# AD9910.net
KiCad netlist of a schematic drawn in Altium Designer
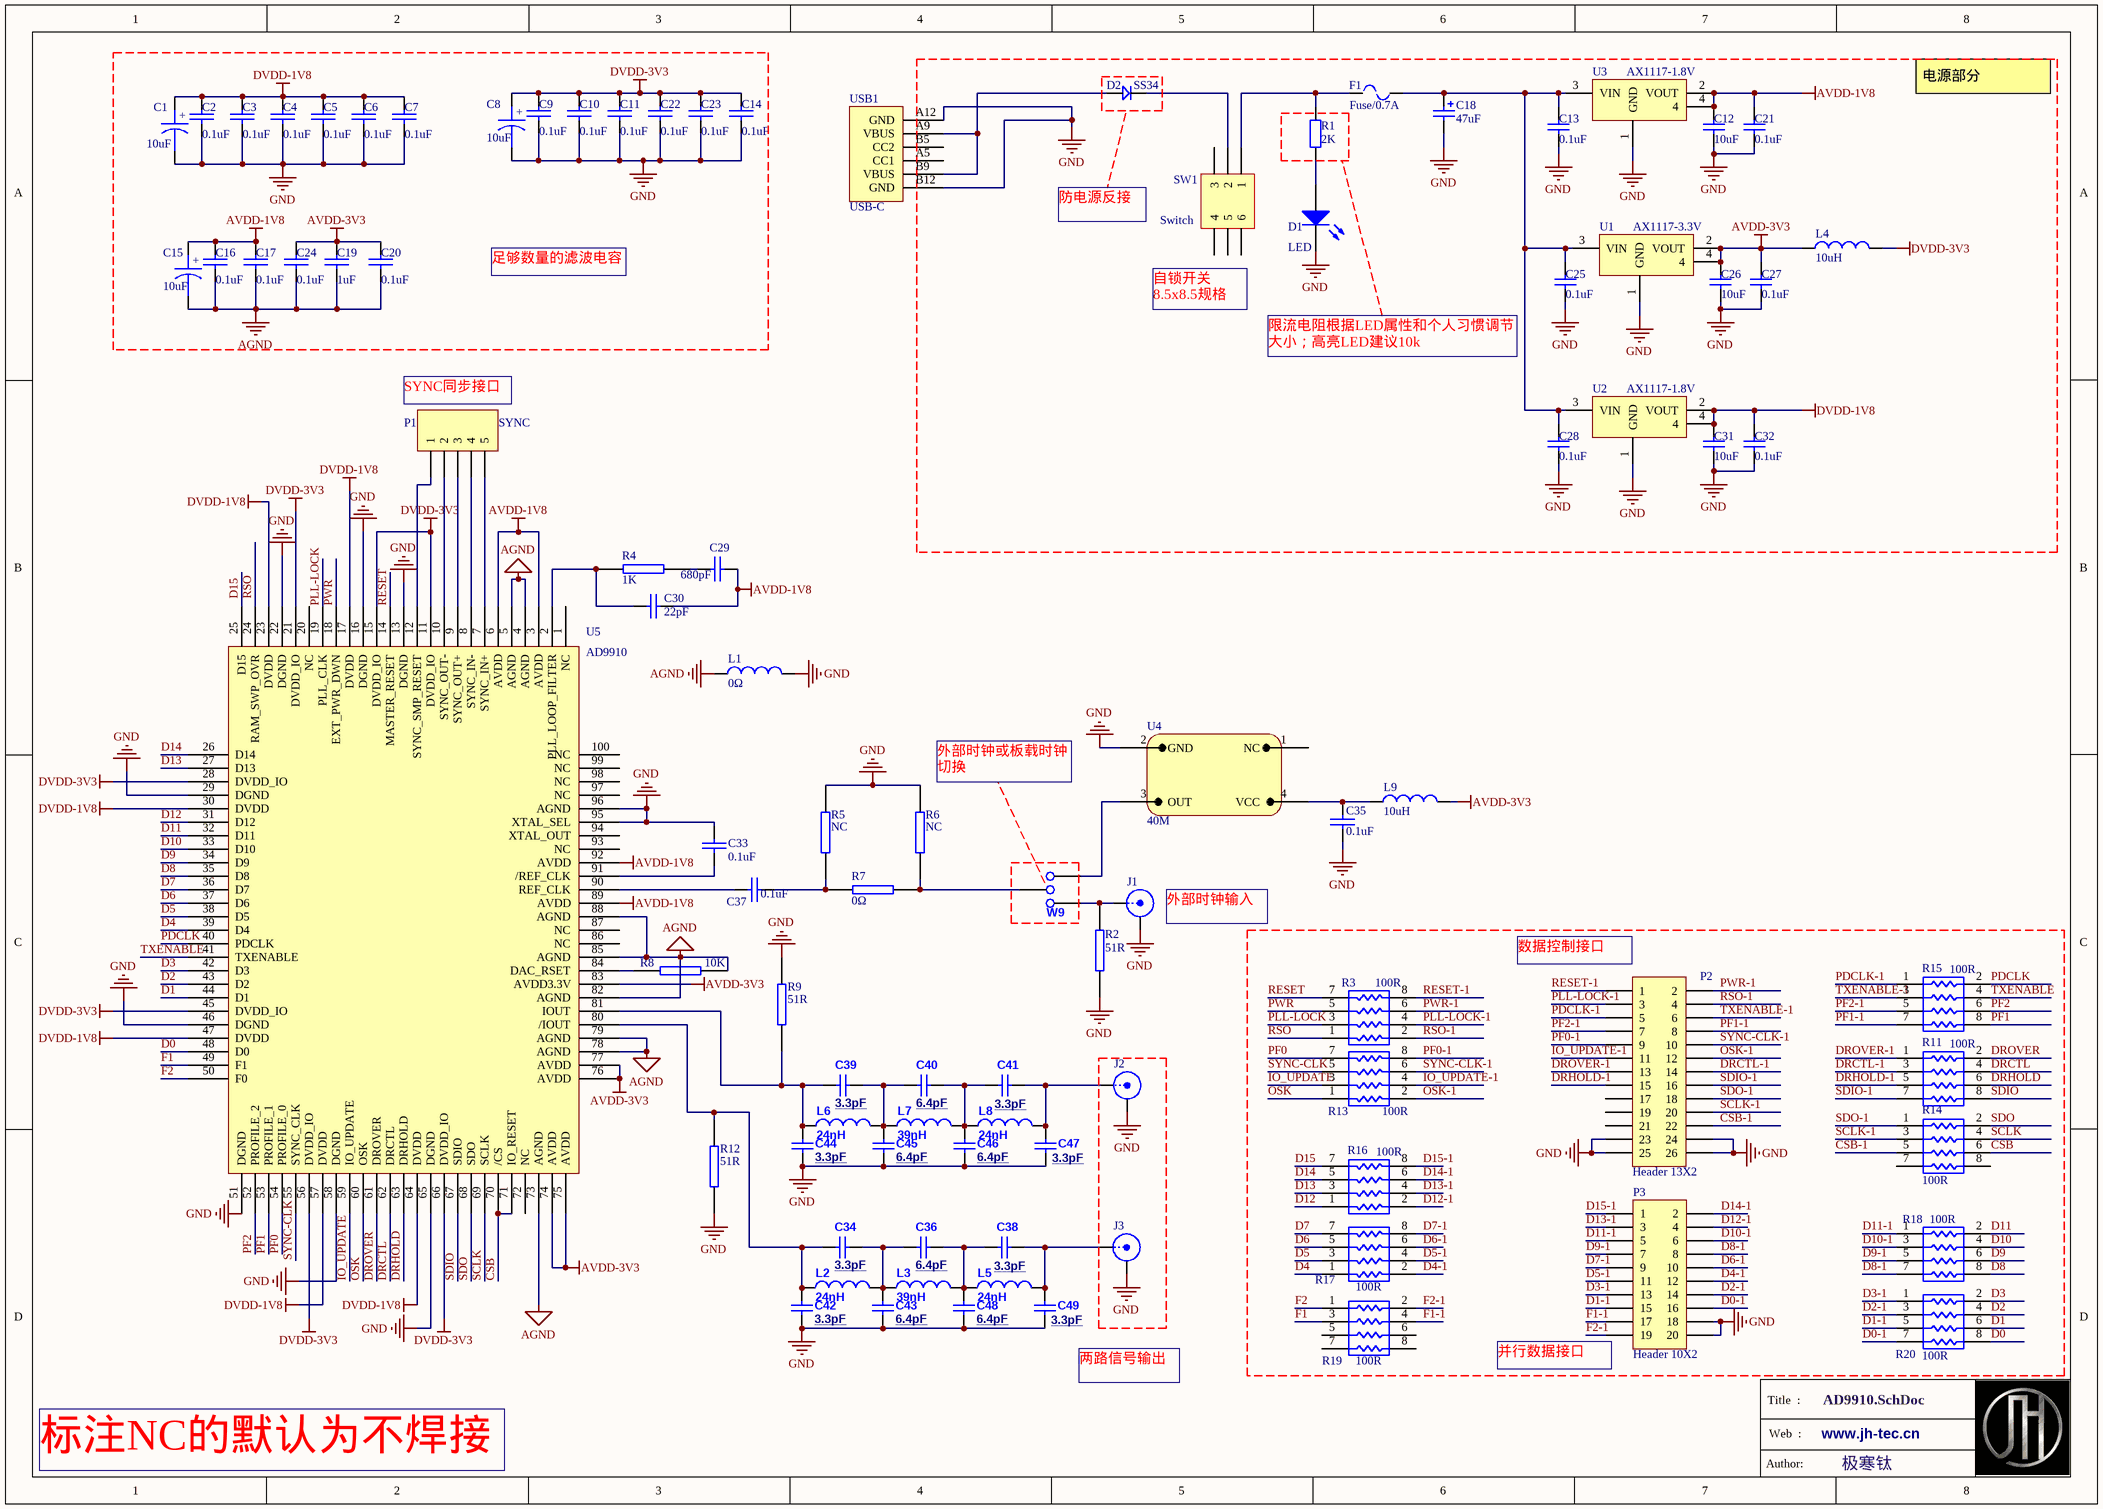
[diagram p0: AD9910.SchDoc]

(export (version "E")
  (design (tool "Eeschema 10.0.6"))
  (components
    (comp (ref "C1")
      (value "10uF")
      (footprint "JH_PCB:C3216")
      (description "Capacitor")
      (libsource (lib "*") (part "CAPACITOR POL"))
    )
    (comp (ref "C2")
      (value "0.1uF")
      (footprint "JH_PCB:C0603")
      (description "Capacitor")
      (libsource (lib "*") (part "CAP"))
    )
    (comp (ref "C3")
      (value "0.1uF")
      (footprint "JH_PCB:C0603")
      (description "Capacitor")
      (libsource (lib "*") (part "CAP"))
    )
    (comp (ref "C4")
      (value "0.1uF")
      (footprint "JH_PCB:C0603")
      (description "Capacitor")
      (libsource (lib "*") (part "CAP"))
    )
    (comp (ref "C5")
      (value "0.1uF")
      (footprint "JH_PCB:C0603")
      (description "Capacitor")
      (libsource (lib "*") (part "CAP"))
    )
    (comp (ref "C6")
      (value "0.1uF")
      (footprint "JH_PCB:C0603")
      (description "Capacitor")
      (libsource (lib "*") (part "CAP"))
    )
    (comp (ref "C7")
      (value "0.1uF")
      (footprint "JH_PCB:C0603")
      (description "Capacitor")
      (libsource (lib "*") (part "CAP"))
    )
    (comp (ref "C8")
      (value "10uF")
      (footprint "JH_PCB:C3216")
      (description "Capacitor")
      (libsource (lib "*") (part "CAPACITOR POL"))
    )
    (comp (ref "C9")
      (value "0.1uF")
      (footprint "JH_PCB:C0603")
      (description "Capacitor")
      (libsource (lib "*") (part "CAP"))
    )
    (comp (ref "C10")
      (value "0.1uF")
      (footprint "JH_PCB:C0603")
      (description "Capacitor")
      (libsource (lib "*") (part "CAP"))
    )
    (comp (ref "C11")
      (value "0.1uF")
      (footprint "JH_PCB:C0603")
      (description "Capacitor")
      (libsource (lib "*") (part "CAP"))
    )
    (comp (ref "C12")
      (value "10uF")
      (footprint "JH_PCB:C3216")
      (description "Capacitor (Semiconductor SIM Model)")
      (fields (field (name "PUBLISHER") "Altium Limited"))
      (libsource (lib "mylib") (part "Cap Semi"))
    )
    (comp (ref "C13")
      (value "0.1uF")
      (footprint "JH_PCB:C0603")
      (description "Capacitor (Semiconductor SIM Model)")
      (fields (field (name "PUBLISHER") "Altium Limited"))
      (libsource (lib "mylib") (part "Cap Semi"))
    )
    (comp (ref "C14")
      (value "0.1uF")
      (footprint "JH_PCB:C0603")
      (description "Capacitor")
      (libsource (lib "*") (part "CAP"))
    )
    (comp (ref "C15")
      (value "10uF")
      (footprint "JH_PCB:C3216")
      (description "Capacitor")
      (libsource (lib "*") (part "CAPACITOR POL"))
    )
    (comp (ref "C16")
      (value "0.1uF")
      (footprint "JH_PCB:C0603")
      (description "Capacitor")
      (libsource (lib "*") (part "CAP"))
    )
    (comp (ref "C17")
      (value "0.1uF")
      (footprint "JH_PCB:C0603")
      (description "Capacitor")
      (libsource (lib "*") (part "CAP"))
    )
    (comp (ref "C18")
      (value "47uF")
      (footprint "JH_PCB:C7343")
      (description "Polarized Capacitor (Surface Mount)")
      (fields (field (name "PUBLISHER") "Altium Limited"))
      (libsource (lib "mylib") (part "Cap Pol3_1"))
    )
    (comp (ref "C19")
      (value "1uF")
      (footprint "JH_PCB:C0603")
      (description "Capacitor")
      (libsource (lib "*") (part "CAP"))
    )
    (comp (ref "C20")
      (value "0.1uF")
      (footprint "JH_PCB:C0603")
      (description "Capacitor")
      (libsource (lib "*") (part "CAP"))
    )
    (comp (ref "C21")
      (value "0.1uF")
      (footprint "JH_PCB:C0603")
      (description "Capacitor (Semiconductor SIM Model)")
      (fields (field (name "PUBLISHER") "Altium Limited"))
      (libsource (lib "mylib") (part "Cap Semi"))
    )
    (comp (ref "C22")
      (value "0.1uF")
      (footprint "JH_PCB:C0603")
      (description "Capacitor")
      (libsource (lib "*") (part "CAP"))
    )
    (comp (ref "C23")
      (value "0.1uF")
      (footprint "JH_PCB:C0603")
      (description "Capacitor")
      (libsource (lib "*") (part "CAP"))
    )
    (comp (ref "C24")
      (value "0.1uF")
      (footprint "JH_PCB:C0603")
      (description "Capacitor")
      (libsource (lib "*") (part "CAP"))
    )
    (comp (ref "C25")
      (value "0.1uF")
      (footprint "JH_PCB:C0603")
      (description "Capacitor (Semiconductor SIM Model)")
      (fields (field (name "PUBLISHER") "Altium Limited"))
      (libsource (lib "mylib") (part "Cap Semi"))
    )
    (comp (ref "C26")
      (value "10uF")
      (footprint "JH_PCB:C3216")
      (description "Capacitor (Semiconductor SIM Model)")
      (fields (field (name "PUBLISHER") "Altium Limited"))
      (libsource (lib "mylib") (part "Cap Semi"))
    )
    (comp (ref "C27")
      (value "0.1uF")
      (footprint "JH_PCB:C0603")
      (description "Capacitor (Semiconductor SIM Model)")
      (fields (field (name "PUBLISHER") "Altium Limited"))
      (libsource (lib "mylib") (part "Cap Semi"))
    )
    (comp (ref "C28")
      (value "0.1uF")
      (footprint "JH_PCB:C0603")
      (description "Capacitor (Semiconductor SIM Model)")
      (fields (field (name "PUBLISHER") "Altium Limited"))
      (libsource (lib "mylib") (part "Cap Semi"))
    )
    (comp (ref "C29")
      (value "680pF")
      (footprint "JH_PCB:C0603")
      (description "Capacitor")
      (libsource (lib "*") (part "CAP"))
    )
    (comp (ref "C30")
      (value "22pF")
      (footprint "JH_PCB:C0603")
      (description "Capacitor")
      (libsource (lib "*") (part "CAP"))
    )
    (comp (ref "C31")
      (value "10uF")
      (footprint "JH_PCB:C3216")
      (description "Capacitor (Semiconductor SIM Model)")
      (fields (field (name "PUBLISHER") "Altium Limited"))
      (libsource (lib "mylib") (part "Cap Semi"))
    )
    (comp (ref "C32")
      (value "0.1uF")
      (footprint "JH_PCB:C0603")
      (description "Capacitor (Semiconductor SIM Model)")
      (fields (field (name "PUBLISHER") "Altium Limited"))
      (libsource (lib "mylib") (part "Cap Semi"))
    )
    (comp (ref "C33")
      (value "0.1uF")
      (footprint "JH_PCB:C0603")
      (description "Capacitor")
      (libsource (lib "*") (part "CAP"))
    )
    (comp (ref "C34")
      (value "3.3pF")
      (footprint "JH_PCB:C0603")
      (description "Capacitor")
      (fields (field (name "PUBLISHER") "Altium Limited"))
      (libsource (lib "Miscellaneous Devices") (part "Cap"))
    )
    (comp (ref "C35")
      (value "0.1uF")
      (footprint "JH_PCB:C0603")
      (description "Capacitor")
      (libsource (lib "*") (part "CAP"))
    )
    (comp (ref "C36")
      (value "6.4pF")
      (footprint "JH_PCB:C0603")
      (description "Capacitor")
      (fields (field (name "PUBLISHER") "Altium Limited"))
      (libsource (lib "Miscellaneous Devices") (part "Cap"))
    )
    (comp (ref "C37")
      (value "0.1uF")
      (footprint "JH_PCB:C0603")
      (description "Capacitor")
      (libsource (lib "*") (part "CAP"))
    )
    (comp (ref "C38")
      (value "3.3pF")
      (footprint "JH_PCB:C0603")
      (description "Capacitor")
      (fields (field (name "PUBLISHER") "Altium Limited"))
      (libsource (lib "Miscellaneous Devices") (part "Cap"))
    )
    (comp (ref "C39")
      (value "3.3pF")
      (footprint "JH_PCB:C0603")
      (description "Capacitor")
      (fields (field (name "PUBLISHER") "Altium Limited"))
      (libsource (lib "Miscellaneous Devices") (part "Cap"))
    )
    (comp (ref "C40")
      (value "6.4pF")
      (footprint "JH_PCB:C0603")
      (description "Capacitor")
      (fields (field (name "PUBLISHER") "Altium Limited"))
      (libsource (lib "Miscellaneous Devices") (part "Cap"))
    )
    (comp (ref "C41")
      (value "3.3pF")
      (footprint "JH_PCB:C0603")
      (description "Capacitor")
      (fields (field (name "PUBLISHER") "Altium Limited"))
      (libsource (lib "Miscellaneous Devices") (part "Cap"))
    )
    (comp (ref "C42")
      (value "3.3pF")
      (footprint "JH_PCB:C0603")
      (description "Capacitor")
      (fields (field (name "PUBLISHER") "Altium Limited"))
      (libsource (lib "Miscellaneous Devices") (part "Cap"))
    )
    (comp (ref "C43")
      (value "6.4pF")
      (footprint "JH_PCB:C0603")
      (description "Capacitor")
      (fields (field (name "PUBLISHER") "Altium Limited"))
      (libsource (lib "Miscellaneous Devices") (part "Cap"))
    )
    (comp (ref "C44")
      (value "3.3pF")
      (footprint "JH_PCB:C0603")
      (description "Capacitor")
      (fields (field (name "PUBLISHER") "Altium Limited"))
      (libsource (lib "Miscellaneous Devices") (part "Cap"))
    )
    (comp (ref "C45")
      (value "6.4pF")
      (footprint "JH_PCB:C0603")
      (description "Capacitor")
      (fields (field (name "PUBLISHER") "Altium Limited"))
      (libsource (lib "Miscellaneous Devices") (part "Cap"))
    )
    (comp (ref "C46")
      (value "6.4pF")
      (footprint "JH_PCB:C0603")
      (description "Capacitor")
      (fields (field (name "PUBLISHER") "Altium Limited"))
      (libsource (lib "Miscellaneous Devices") (part "Cap"))
    )
    (comp (ref "C47")
      (value "3.3pF")
      (footprint "JH_PCB:C0603")
      (description "Capacitor")
      (fields (field (name "PUBLISHER") "Altium Limited"))
      (libsource (lib "Miscellaneous Devices") (part "Cap"))
    )
    (comp (ref "C48")
      (value "6.4pF")
      (footprint "JH_PCB:C0603")
      (description "Capacitor")
      (fields (field (name "PUBLISHER") "Altium Limited"))
      (libsource (lib "Miscellaneous Devices") (part "Cap"))
    )
    (comp (ref "C49")
      (value "3.3pF")
      (footprint "JH_PCB:C0603")
      (description "Capacitor")
      (fields (field (name "PUBLISHER") "Altium Limited"))
      (libsource (lib "Miscellaneous Devices") (part "Cap"))
    )
    (comp (ref "D1")
      (value "LED")
      (footprint "JH_PCB:LED_GREEN_0603")
      (fields (field (name "PUBLISHER") "Altium Limited"))
      (libsource (lib "Xiaowei") (part "LED"))
    )
    (comp (ref "D2")
      (value "SS34")
      (footprint "JH_PCB:DO-214AC")
      (description "1N4148")
      (libsource (lib "ATK-SIM900A") (part "D"))
    )
    (comp (ref "F1") (value "Fuse/0.7A") (footprint "JH_PCB:1812") (libsource (lib "常用sch") (part "Fuse")))
    (comp (ref "J1")
      (value "SMB")
      (footprint "JH_PCB:SMA_RJ45")
      (description "SMB Straight Connector")
      (fields (field (name "PUBLISHER") "Altium Limited"))
      (libsource (lib "Miscellaneous Connectors") (part "SMB"))
    )
    (comp (ref "J2")
      (value "SMB")
      (footprint "JH_PCB:SMA_3D")
      (description "SMB Straight Connector")
      (fields (field (name "PUBLISHER") "Altium Limited"))
      (libsource (lib "Miscellaneous Connectors") (part "SMB"))
    )
    (comp (ref "J3")
      (value "SMB")
      (footprint "JH_PCB:SMA_3D")
      (description "SMB Straight Connector")
      (fields (field (name "PUBLISHER") "Altium Limited"))
      (libsource (lib "Miscellaneous Connectors") (part "SMB"))
    )
    (comp (ref "L1")
      (value "0Ω")
      (footprint "JH_PCB:L0805")
      (description "Inductor")
      (fields (field (name "PUBLISHER") "Altium Limited"))
      (libsource (lib "Miscellaneous Devices") (part "Inductor"))
    )
    (comp (ref "L2")
      (value "24nH")
      (footprint "JH_PCB:L0603")
      (description "Inductor")
      (fields (field (name "PUBLISHER") "Altium Limited"))
      (libsource (lib "Miscellaneous Devices") (part "Inductor"))
    )
    (comp (ref "L3")
      (value "39nH")
      (footprint "JH_PCB:L0603")
      (description "Inductor")
      (fields (field (name "PUBLISHER") "Altium Limited"))
      (libsource (lib "Miscellaneous Devices") (part "Inductor"))
    )
    (comp (ref "L4")
      (value "10uH")
      (footprint "JH_PCB:L0805")
      (description "Inductor")
      (fields (field (name "PUBLISHER") "Altium Limited"))
      (libsource (lib "Miscellaneous Devices") (part "Inductor"))
    )
    (comp (ref "L5")
      (value "24nH")
      (footprint "JH_PCB:L0603")
      (description "Inductor")
      (fields (field (name "PUBLISHER") "Altium Limited"))
      (libsource (lib "Miscellaneous Devices") (part "Inductor"))
    )
    (comp (ref "L6")
      (value "24nH")
      (footprint "JH_PCB:L0603")
      (description "Inductor")
      (fields (field (name "PUBLISHER") "Altium Limited"))
      (libsource (lib "Miscellaneous Devices") (part "Inductor"))
    )
    (comp (ref "L7")
      (value "39nH")
      (footprint "JH_PCB:L0603")
      (description "Inductor")
      (fields (field (name "PUBLISHER") "Altium Limited"))
      (libsource (lib "Miscellaneous Devices") (part "Inductor"))
    )
    (comp (ref "L8")
      (value "24nH")
      (footprint "JH_PCB:L0603")
      (description "Inductor")
      (fields (field (name "PUBLISHER") "Altium Limited"))
      (libsource (lib "Miscellaneous Devices") (part "Inductor"))
    )
    (comp (ref "L9")
      (value "10uH")
      (footprint "JH_PCB:L0805")
      (description "Inductor")
      (fields (field (name "PUBLISHER") "Altium Limited"))
      (libsource (lib "Miscellaneous Devices") (part "Inductor"))
    )
    (comp (ref "P1")
      (value "SYNC")
      (footprint "JH_PCB:HDR1X5")
      (description "Header, 5-Pin")
      (fields (field (name "PUBLISHER") "Altium Limited"))
      (libsource (lib "Miscellaneous Connectors") (part "Header 5"))
    )
    (comp (ref "P2")
      (value "Header 13X2")
      (footprint "JH_PCB:HDR2X13")
      (description "Header, 13-Pin, Dual row")
      (fields (field (name "PUBLISHER") "Altium Limited"))
      (libsource (lib "Miscellaneous Connectors") (part "Header 13X2"))
    )
    (comp (ref "P3")
      (value "Header 10X2")
      (footprint "JH_PCB:HDR2X10")
      (description "Header, 10-Pin, Dual row")
      (fields (field (name "PUBLISHER") "Altium Limited"))
      (libsource (lib "Miscellaneous Connectors") (part "Header 10X2"))
    )
    (comp (ref "R1")
      (value "2K")
      (footprint "JH_PCB:R0603")
      (description "Resistor")
      (fields (field (name "PUBLISHER") "Altium Limited"))
      (libsource (lib "Miscellaneous Devices") (part "Res2"))
    )
    (comp (ref "R2") (value "51R") (footprint "JH_PCB:R0603") (libsource (lib "*") (part "RES2")))
    (comp (ref "R3") (value "100R") (footprint "JH_PCB:RA4") (libsource (lib "常用sch") (part "RESPACK1")))
    (comp (ref "R4") (value "1K") (footprint "JH_PCB:R0603") (libsource (lib "*") (part "RES2")))
    (comp (ref "R5") (value "NC") (footprint "JH_PCB:R0603") (libsource (lib "*") (part "RES2")))
    (comp (ref "R6") (value "NC") (footprint "JH_PCB:R0603") (libsource (lib "*") (part "RES2")))
    (comp (ref "R7") (value "0Ω") (footprint "JH_PCB:R0603") (libsource (lib "*") (part "RES2")))
    (comp (ref "R8") (value "10K") (footprint "JH_PCB:R0603") (libsource (lib "*") (part "RES2")))
    (comp (ref "R9") (value "51R") (footprint "JH_PCB:R0603") (libsource (lib "*") (part "RES2")))
    (comp (ref "R11") (value "100R") (footprint "JH_PCB:RA4") (libsource (lib "常用sch") (part "RESPACK1")))
    (comp (ref "R12") (value "51R") (footprint "JH_PCB:R0603") (libsource (lib "*") (part "RES2")))
    (comp (ref "R13") (value "100R") (footprint "JH_PCB:RA4") (libsource (lib "常用sch") (part "RESPACK1")))
    (comp (ref "R14") (value "100R") (footprint "JH_PCB:RA4") (libsource (lib "常用sch") (part "RESPACK1")))
    (comp (ref "R15") (value "100R") (footprint "JH_PCB:RA4") (libsource (lib "常用sch") (part "RESPACK1")))
    (comp (ref "R16") (value "100R") (footprint "JH_PCB:RA4") (libsource (lib "常用sch") (part "RESPACK1")))
    (comp (ref "R17") (value "100R") (footprint "JH_PCB:RA4") (libsource (lib "常用sch") (part "RESPACK1")))
    (comp (ref "R18") (value "100R") (footprint "JH_PCB:RA4") (libsource (lib "常用sch") (part "RESPACK1")))
    (comp (ref "R19") (value "100R") (footprint "JH_PCB:RA4") (libsource (lib "常用sch") (part "RESPACK1")))
    (comp (ref "R20") (value "100R") (footprint "JH_PCB:RA4") (libsource (lib "常用sch") (part "RESPACK1")))
    (comp (ref "SW1")
      (value "Switch")
      (footprint "JH_PCB:SW6_8.5*8.5")
      (libsource (lib "常用sch") (part "SW6"))
    )
    (comp (ref "U1")
      (value "AX1117-3.3V")
      (footprint "JH_PCB:SOT-223")
      (libsource (lib "常用sch") (part "AMS1117"))
    )
    (comp (ref "U2")
      (value "AX1117-1.8V")
      (footprint "JH_PCB:SOT-223")
      (libsource (lib "常用sch") (part "AMS1117"))
    )
    (comp (ref "U3")
      (value "AX1117-1.8V")
      (footprint "JH_PCB:SOT-223")
      (libsource (lib "常用sch") (part "AMS1117"))
    )
    (comp (ref "U4") (value "40M") (footprint "JH_PCB:X7050_4P") (libsource (lib "*") (part "CRYS2")))
    (comp (ref "U5") (value "AD9910") (footprint "JH_PCB:TQFP100") (libsource (lib "常用sch") (part "AD9910")))
    (comp (ref "USB1")
      (value "USB-C")
      (footprint "USB-C/S_C")
      (description "USB-C_6P型母接口")
      (libsource (lib "接口") (part "USB-C_6P/S"))
    )
    (comp (ref "W9")
      (value "key")
      (footprint "JH_PCB:HDR1X3")
      (description "KEY 1 to 2")
      (libsource (lib "*") (part "W"))
    )
  )
  (nets
    (net (code "1") (name "/CSB") (class "Default")
      (node (ref "R14") (pin "6") (pinfunction "6_6") (pintype "passive"))
      (node (ref "U5") (pin "70") (pinfunction "/CS_70") (pintype "passive"))
      (node (ref "U5") (pin "71") (pinfunction "IO_RESET_71") (pintype "passive"))
    )
    (net (code "2") (name "/CSB-1") (class "Default")
      (node (ref "P2") (pin "22") (pinfunction "22_22") (pintype "passive"))
      (node (ref "R14") (pin "5") (pinfunction "5_5") (pintype "passive"))
    )
    (net (code "3") (name "/D0") (class "Default")
      (node (ref "R20") (pin "8") (pinfunction "8_8") (pintype "passive"))
      (node (ref "U5") (pin "48") (pinfunction "D0_48") (pintype "passive"))
    )
    (net (code "4") (name "/D0-1") (class "Default")
      (node (ref "P3") (pin "16") (pinfunction "16_16") (pintype "passive"))
      (node (ref "R20") (pin "7") (pinfunction "7_7") (pintype "passive"))
    )
    (net (code "5") (name "/D1") (class "Default")
      (node (ref "R20") (pin "6") (pinfunction "6_6") (pintype "passive"))
      (node (ref "U5") (pin "44") (pinfunction "D1_44") (pintype "passive"))
    )
    (net (code "6") (name "/D1-1") (class "Default")
      (node (ref "P3") (pin "15") (pinfunction "15_15") (pintype "passive"))
      (node (ref "R20") (pin "5") (pinfunction "5_5") (pintype "passive"))
    )
    (net (code "7") (name "/D2") (class "Default")
      (node (ref "R20") (pin "4") (pinfunction "4_4") (pintype "passive"))
      (node (ref "U5") (pin "43") (pinfunction "D2_43") (pintype "passive"))
    )
    (net (code "8") (name "/D2-1") (class "Default")
      (node (ref "P3") (pin "14") (pinfunction "14_14") (pintype "passive"))
      (node (ref "R20") (pin "3") (pinfunction "3_3") (pintype "passive"))
    )
    (net (code "9") (name "/D3") (class "Default")
      (node (ref "R20") (pin "2") (pinfunction "2_2") (pintype "passive"))
      (node (ref "U5") (pin "42") (pinfunction "D3_42") (pintype "passive"))
    )
    (net (code "10") (name "/D3-1") (class "Default")
      (node (ref "P3") (pin "13") (pinfunction "13_13") (pintype "passive"))
      (node (ref "R20") (pin "1") (pinfunction "1_1") (pintype "passive"))
    )
    (net (code "11") (name "/D4") (class "Default")
      (node (ref "R17") (pin "1") (pinfunction "1_1") (pintype "passive"))
      (node (ref "U5") (pin "39") (pinfunction "D4_39") (pintype "passive"))
    )
    (net (code "12") (name "/D4-1") (class "Default")
      (node (ref "P3") (pin "12") (pinfunction "12_12") (pintype "passive"))
      (node (ref "R17") (pin "2") (pinfunction "2_2") (pintype "passive"))
    )
    (net (code "13") (name "/D5") (class "Default")
      (node (ref "R17") (pin "3") (pinfunction "3_3") (pintype "passive"))
      (node (ref "U5") (pin "38") (pinfunction "D5_38") (pintype "passive"))
    )
    (net (code "14") (name "/D5-1") (class "Default")
      (node (ref "P3") (pin "11") (pinfunction "11_11") (pintype "passive"))
      (node (ref "R17") (pin "4") (pinfunction "4_4") (pintype "passive"))
    )
    (net (code "15") (name "/D6") (class "Default")
      (node (ref "R17") (pin "5") (pinfunction "5_5") (pintype "passive"))
      (node (ref "U5") (pin "37") (pinfunction "D6_37") (pintype "passive"))
    )
    (net (code "16") (name "/D6-1") (class "Default")
      (node (ref "P3") (pin "10") (pinfunction "10_10") (pintype "passive"))
      (node (ref "R17") (pin "6") (pinfunction "6_6") (pintype "passive"))
    )
    (net (code "17") (name "/D7") (class "Default")
      (node (ref "R17") (pin "7") (pinfunction "7_7") (pintype "passive"))
      (node (ref "U5") (pin "36") (pinfunction "D7_36") (pintype "passive"))
    )
    (net (code "18") (name "/D7-1") (class "Default")
      (node (ref "P3") (pin "9") (pinfunction "9_9") (pintype "passive"))
      (node (ref "R17") (pin "8") (pinfunction "8_8") (pintype "passive"))
    )
    (net (code "19") (name "/D8") (class "Default")
      (node (ref "R18") (pin "8") (pinfunction "8_8") (pintype "passive"))
      (node (ref "U5") (pin "35") (pinfunction "D8_35") (pintype "passive"))
    )
    (net (code "20") (name "/D8-1") (class "Default")
      (node (ref "P3") (pin "8") (pinfunction "8_8") (pintype "passive"))
      (node (ref "R18") (pin "7") (pinfunction "7_7") (pintype "passive"))
    )
    (net (code "21") (name "/D9") (class "Default")
      (node (ref "R18") (pin "6") (pinfunction "6_6") (pintype "passive"))
      (node (ref "U5") (pin "34") (pinfunction "D9_34") (pintype "passive"))
    )
    (net (code "22") (name "/D9-1") (class "Default")
      (node (ref "P3") (pin "7") (pinfunction "7_7") (pintype "passive"))
      (node (ref "R18") (pin "5") (pinfunction "5_5") (pintype "passive"))
    )
    (net (code "23") (name "/D10") (class "Default")
      (node (ref "R18") (pin "4") (pinfunction "4_4") (pintype "passive"))
      (node (ref "U5") (pin "33") (pinfunction "D10_33") (pintype "passive"))
    )
    (net (code "24") (name "/D10-1") (class "Default")
      (node (ref "P3") (pin "6") (pinfunction "6_6") (pintype "passive"))
      (node (ref "R18") (pin "3") (pinfunction "3_3") (pintype "passive"))
    )
    (net (code "25") (name "/D11") (class "Default")
      (node (ref "R18") (pin "2") (pinfunction "2_2") (pintype "passive"))
      (node (ref "U5") (pin "32") (pinfunction "D11_32") (pintype "passive"))
    )
    (net (code "26") (name "/D11-1") (class "Default")
      (node (ref "P3") (pin "5") (pinfunction "5_5") (pintype "passive"))
      (node (ref "R18") (pin "1") (pinfunction "1_1") (pintype "passive"))
    )
    (net (code "27") (name "/D12") (class "Default")
      (node (ref "R16") (pin "1") (pinfunction "1_1") (pintype "passive"))
      (node (ref "U5") (pin "31") (pinfunction "D12_31") (pintype "passive"))
    )
    (net (code "28") (name "/D12-1") (class "Default")
      (node (ref "P3") (pin "4") (pinfunction "4_4") (pintype "passive"))
      (node (ref "R16") (pin "2") (pinfunction "2_2") (pintype "passive"))
    )
    (net (code "29") (name "/D13") (class "Default")
      (node (ref "R16") (pin "3") (pinfunction "3_3") (pintype "passive"))
      (node (ref "U5") (pin "27") (pinfunction "D13_27") (pintype "passive"))
    )
    (net (code "30") (name "/D13-1") (class "Default")
      (node (ref "P3") (pin "3") (pinfunction "3_3") (pintype "passive"))
      (node (ref "R16") (pin "4") (pinfunction "4_4") (pintype "passive"))
    )
    (net (code "31") (name "/D14") (class "Default")
      (node (ref "R16") (pin "5") (pinfunction "5_5") (pintype "passive"))
      (node (ref "U5") (pin "26") (pinfunction "D14_26") (pintype "passive"))
    )
    (net (code "32") (name "/D14-1") (class "Default")
      (node (ref "P3") (pin "2") (pinfunction "2_2") (pintype "passive"))
      (node (ref "R16") (pin "6") (pinfunction "6_6") (pintype "passive"))
    )
    (net (code "33") (name "/D15") (class "Default")
      (node (ref "R16") (pin "7") (pinfunction "7_7") (pintype "passive"))
      (node (ref "U5") (pin "25") (pinfunction "D15_25") (pintype "passive"))
    )
    (net (code "34") (name "/D15-1") (class "Default")
      (node (ref "P3") (pin "1") (pinfunction "1_1") (pintype "passive"))
      (node (ref "R16") (pin "8") (pinfunction "8_8") (pintype "passive"))
    )
    (net (code "35") (name "/DRCTL") (class "Default")
      (node (ref "R11") (pin "4") (pinfunction "4_4") (pintype "passive"))
      (node (ref "U5") (pin "62") (pinfunction "DRCTL_62") (pintype "passive"))
    )
    (net (code "36") (name "/DRCTL-1") (class "Default")
      (node (ref "P2") (pin "14") (pinfunction "14_14") (pintype "passive"))
      (node (ref "R11") (pin "3") (pinfunction "3_3") (pintype "passive"))
    )
    (net (code "37") (name "/DRHOLD") (class "Default")
      (node (ref "R11") (pin "6") (pinfunction "6_6") (pintype "passive"))
      (node (ref "U5") (pin "63") (pinfunction "DRHOLD_63") (pintype "passive"))
    )
    (net (code "38") (name "/DRHOLD-1") (class "Default")
      (node (ref "P2") (pin "15") (pinfunction "15_15") (pintype "passive"))
      (node (ref "R11") (pin "5") (pinfunction "5_5") (pintype "passive"))
    )
    (net (code "39") (name "/DROVER") (class "Default")
      (node (ref "R11") (pin "2") (pinfunction "2_2") (pintype "passive"))
      (node (ref "U5") (pin "61") (pinfunction "DROVER_61") (pintype "passive"))
    )
    (net (code "40") (name "/DROVER-1") (class "Default")
      (node (ref "P2") (pin "13") (pinfunction "13_13") (pintype "passive"))
      (node (ref "R11") (pin "1") (pinfunction "1_1") (pintype "passive"))
    )
    (net (code "41") (name "/F1") (class "Default")
      (node (ref "R19") (pin "3") (pinfunction "3_3") (pintype "passive"))
      (node (ref "U5") (pin "49") (pinfunction "F1_49") (pintype "passive"))
    )
    (net (code "42") (name "/F1-1") (class "Default")
      (node (ref "P3") (pin "17") (pinfunction "17_17") (pintype "passive"))
      (node (ref "R19") (pin "4") (pinfunction "4_4") (pintype "passive"))
    )
    (net (code "43") (name "/F2") (class "Default")
      (node (ref "R19") (pin "1") (pinfunction "1_1") (pintype "passive"))
      (node (ref "U5") (pin "50") (pinfunction "F0_50") (pintype "passive"))
    )
    (net (code "44") (name "/F2-1") (class "Default")
      (node (ref "P3") (pin "19") (pinfunction "19_19") (pintype "passive"))
      (node (ref "R19") (pin "2") (pinfunction "2_2") (pintype "passive"))
    )
    (net (code "45") (name "/IO_UPDATE") (class "Default")
      (node (ref "R13") (pin "3") (pinfunction "3_3") (pintype "passive"))
      (node (ref "U5") (pin "59") (pinfunction "IO_UPDATE_59") (pintype "passive"))
    )
    (net (code "46") (name "/IO_UPDATE-1") (class "Default")
      (node (ref "P2") (pin "11") (pinfunction "11_11") (pintype "passive"))
      (node (ref "R13") (pin "4") (pinfunction "4_4") (pintype "passive"))
    )
    (net (code "47") (name "/OSK") (class "Default")
      (node (ref "R13") (pin "1") (pinfunction "1_1") (pintype "passive"))
      (node (ref "U5") (pin "60") (pinfunction "OSK_60") (pintype "passive"))
    )
    (net (code "48") (name "/OSK-1") (class "Default")
      (node (ref "P2") (pin "12") (pinfunction "12_12") (pintype "passive"))
      (node (ref "R13") (pin "2") (pinfunction "2_2") (pintype "passive"))
    )
    (net (code "49") (name "/PDCLK") (class "Default")
      (node (ref "R15") (pin "2") (pinfunction "2_2") (pintype "passive"))
      (node (ref "U5") (pin "40") (pinfunction "PDCLK_40") (pintype "passive"))
    )
    (net (code "50") (name "/PDCLK-1") (class "Default")
      (node (ref "P2") (pin "5") (pinfunction "5_5") (pintype "passive"))
      (node (ref "R15") (pin "1") (pinfunction "1_1") (pintype "passive"))
    )
    (net (code "51") (name "/PF0") (class "Default")
      (node (ref "R13") (pin "7") (pinfunction "7_7") (pintype "passive"))
      (node (ref "U5") (pin "54") (pinfunction "PROFILE_0_54") (pintype "passive"))
    )
    (net (code "52") (name "/PF0-1") (class "Default")
      (node (ref "P2") (pin "9") (pinfunction "9_9") (pintype "passive"))
      (node (ref "R13") (pin "8") (pinfunction "8_8") (pintype "passive"))
    )
    (net (code "53") (name "/PF1") (class "Default")
      (node (ref "R15") (pin "8") (pinfunction "8_8") (pintype "passive"))
      (node (ref "U5") (pin "53") (pinfunction "PROFILE_1_53") (pintype "passive"))
    )
    (net (code "54") (name "/PF1-1") (class "Default")
      (node (ref "P2") (pin "8") (pinfunction "8_8") (pintype "passive"))
      (node (ref "R15") (pin "7") (pinfunction "7_7") (pintype "passive"))
    )
    (net (code "55") (name "/PF2") (class "Default")
      (node (ref "R15") (pin "6") (pinfunction "6_6") (pintype "passive"))
      (node (ref "U5") (pin "52") (pinfunction "PROFILE_2_52") (pintype "passive"))
    )
    (net (code "56") (name "/PF2-1") (class "Default")
      (node (ref "P2") (pin "7") (pinfunction "7_7") (pintype "passive"))
      (node (ref "R15") (pin "5") (pinfunction "5_5") (pintype "passive"))
    )
    (net (code "57") (name "/PLL-LOCK") (class "Default")
      (node (ref "R3") (pin "3") (pinfunction "3_3") (pintype "passive"))
      (node (ref "U5") (pin "19") (pinfunction "PLL_CLK_19") (pintype "passive"))
    )
    (net (code "58") (name "/PLL-LOCK-1") (class "Default")
      (node (ref "P2") (pin "3") (pinfunction "3_3") (pintype "passive"))
      (node (ref "R3") (pin "4") (pinfunction "4_4") (pintype "passive"))
    )
    (net (code "59") (name "/PWR") (class "Default")
      (node (ref "R3") (pin "5") (pinfunction "5_5") (pintype "passive"))
      (node (ref "U5") (pin "18") (pinfunction "EXT_PWR_DWN_18") (pintype "passive"))
    )
    (net (code "60") (name "/PWR-1") (class "Default")
      (node (ref "P2") (pin "2") (pinfunction "2_2") (pintype "passive"))
      (node (ref "R3") (pin "6") (pinfunction "6_6") (pintype "passive"))
    )
    (net (code "61") (name "/RESET") (class "Default")
      (node (ref "R3") (pin "7") (pinfunction "7_7") (pintype "passive"))
      (node (ref "U5") (pin "14") (pinfunction "MASTER_RESET_14") (pintype "passive"))
    )
    (net (code "62") (name "/RESET-1") (class "Default")
      (node (ref "P2") (pin "1") (pinfunction "1_1") (pintype "passive"))
      (node (ref "R3") (pin "8") (pinfunction "8_8") (pintype "passive"))
    )
    (net (code "63") (name "/RSO") (class "Default")
      (node (ref "R3") (pin "1") (pinfunction "1_1") (pintype "passive"))
      (node (ref "U5") (pin "24") (pinfunction "RAM_SWP_OVR_24") (pintype "passive"))
    )
    (net (code "64") (name "/RSO-1") (class "Default")
      (node (ref "P2") (pin "4") (pinfunction "4_4") (pintype "passive"))
      (node (ref "R3") (pin "2") (pinfunction "2_2") (pintype "passive"))
    )
    (net (code "65") (name "/SCLK") (class "Default")
      (node (ref "R14") (pin "4") (pinfunction "4_4") (pintype "passive"))
      (node (ref "U5") (pin "69") (pinfunction "SCLK_69") (pintype "passive"))
    )
    (net (code "66") (name "/SCLK-1") (class "Default")
      (node (ref "P2") (pin "20") (pinfunction "20_20") (pintype "passive"))
      (node (ref "R14") (pin "3") (pinfunction "3_3") (pintype "passive"))
    )
    (net (code "67") (name "/SDIO") (class "Default")
      (node (ref "R11") (pin "8") (pinfunction "8_8") (pintype "passive"))
      (node (ref "U5") (pin "67") (pinfunction "SDIO_67") (pintype "passive"))
    )
    (net (code "68") (name "/SDIO-1") (class "Default")
      (node (ref "P2") (pin "16") (pinfunction "16_16") (pintype "passive"))
      (node (ref "R11") (pin "7") (pinfunction "7_7") (pintype "passive"))
    )
    (net (code "69") (name "/SDO") (class "Default")
      (node (ref "R14") (pin "2") (pinfunction "2_2") (pintype "passive"))
      (node (ref "U5") (pin "68") (pinfunction "SDO_68") (pintype "passive"))
    )
    (net (code "70") (name "/SDO-1") (class "Default")
      (node (ref "P2") (pin "18") (pinfunction "18_18") (pintype "passive"))
      (node (ref "R14") (pin "1") (pinfunction "1_1") (pintype "passive"))
    )
    (net (code "71") (name "/SYNC-CLK") (class "Default")
      (node (ref "R13") (pin "5") (pinfunction "5_5") (pintype "passive"))
      (node (ref "U5") (pin "55") (pinfunction "SYNC_CLK_55") (pintype "passive"))
    )
    (net (code "72") (name "/SYNC-CLK-1") (class "Default")
      (node (ref "P2") (pin "10") (pinfunction "10_10") (pintype "passive"))
      (node (ref "R13") (pin "6") (pinfunction "6_6") (pintype "passive"))
    )
    (net (code "73") (name "/TXENABLE") (class "Default")
      (node (ref "R15") (pin "4") (pinfunction "4_4") (pintype "passive"))
      (node (ref "U5") (pin "41") (pinfunction "TXENABLE_41") (pintype "passive"))
    )
    (net (code "74") (name "/TXENABLE-1") (class "Default")
      (node (ref "P2") (pin "6") (pinfunction "6_6") (pintype "passive"))
      (node (ref "R15") (pin "3") (pinfunction "3_3") (pintype "passive"))
    )
    (net (code "75") (name "AGND") (class "Default")
      (node (ref "C15") (pin "2") (pinfunction "2_2") (pintype "passive"))
      (node (ref "C16") (pin "2") (pinfunction "2_2") (pintype "passive"))
      (node (ref "C17") (pin "2") (pinfunction "2_2") (pintype "passive"))
      (node (ref "C19") (pin "2") (pinfunction "2_2") (pintype "passive"))
      (node (ref "C20") (pin "2") (pinfunction "2_2") (pintype "passive"))
      (node (ref "C24") (pin "2") (pinfunction "2_2") (pintype "passive"))
      (node (ref "L1") (pin "1") (pinfunction "1_1") (pintype "passive"))
      (node (ref "R8") (pin "1") (pinfunction "1_1") (pintype "passive"))
      (node (ref "U5") (pin "4") (pinfunction "AGND_4") (pintype "passive"))
      (node (ref "U5") (pin "5") (pinfunction "AGND_5") (pintype "passive"))
      (node (ref "U5") (pin "73") (pinfunction "AGND_73") (pintype "passive"))
      (node (ref "U5") (pin "78") (pinfunction "AGND_78") (pintype "passive"))
      (node (ref "U5") (pin "79") (pinfunction "AGND_79") (pintype "passive"))
      (node (ref "U5") (pin "82") (pinfunction "AGND_82") (pintype "passive"))
      (node (ref "U5") (pin "85") (pinfunction "AGND_85") (pintype "passive"))
      (node (ref "U5") (pin "88") (pinfunction "AGND_88") (pintype "passive"))
    )
    (net (code "76") (name "AVDD-1V8") (class "Default")
      (node (ref "C12") (pin "2") (pinfunction "2_2") (pintype "passive"))
      (node (ref "C15") (pin "1") (pinfunction "1_1") (pintype "passive"))
      (node (ref "C16") (pin "1") (pinfunction "1_1") (pintype "passive"))
      (node (ref "C17") (pin "1") (pinfunction "1_1") (pintype "passive"))
      (node (ref "C21") (pin "1") (pinfunction "1_1") (pintype "passive"))
      (node (ref "C29") (pin "2") (pinfunction "2_2") (pintype "passive"))
      (node (ref "C30") (pin "2") (pinfunction "2_2") (pintype "passive"))
      (node (ref "U3") (pin "2") (pinfunction "VOUT_2") (pintype "passive"))
      (node (ref "U3") (pin "4") (pinfunction "4_4") (pintype "passive"))
      (node (ref "U5") (pin "3") (pinfunction "AVDD_3") (pintype "passive"))
      (node (ref "U5") (pin "6") (pinfunction "AVDD_6") (pintype "passive"))
      (node (ref "U5") (pin "89") (pinfunction "AVDD_89") (pintype "passive"))
      (node (ref "U5") (pin "92") (pinfunction "AVDD_92") (pintype "passive"))
    )
    (net (code "77") (name "AVDD-3V3") (class "Default")
      (node (ref "C19") (pin "1") (pinfunction "1_1") (pintype "passive"))
      (node (ref "C20") (pin "1") (pinfunction "1_1") (pintype "passive"))
      (node (ref "C24") (pin "1") (pinfunction "1_1") (pintype "passive"))
      (node (ref "C26") (pin "2") (pinfunction "2_2") (pintype "passive"))
      (node (ref "C27") (pin "1") (pinfunction "1_1") (pintype "passive"))
      (node (ref "L4") (pin "1") (pinfunction "1_1") (pintype "passive"))
      (node (ref "L9") (pin "2") (pinfunction "2_2") (pintype "passive"))
      (node (ref "U1") (pin "2") (pinfunction "VOUT_2") (pintype "passive"))
      (node (ref "U1") (pin "4") (pinfunction "4_4") (pintype "passive"))
      (node (ref "U5") (pin "74") (pinfunction "AVDD_74") (pintype "passive"))
      (node (ref "U5") (pin "75") (pinfunction "AVDD_75") (pintype "passive"))
      (node (ref "U5") (pin "76") (pinfunction "AVDD_76") (pintype "passive"))
      (node (ref "U5") (pin "77") (pinfunction "AVDD_77") (pintype "passive"))
      (node (ref "U5") (pin "83") (pinfunction "AVDD3.3V_83") (pintype "passive"))
    )
    (net (code "78") (name "DVDD-1V8") (class "Default")
      (node (ref "C1") (pin "1") (pinfunction "1_1") (pintype "passive"))
      (node (ref "C2") (pin "1") (pinfunction "1_1") (pintype "passive"))
      (node (ref "C3") (pin "1") (pinfunction "1_1") (pintype "passive"))
      (node (ref "C31") (pin "2") (pinfunction "2_2") (pintype "passive"))
      (node (ref "C32") (pin "1") (pinfunction "1_1") (pintype "passive"))
      (node (ref "C4") (pin "1") (pinfunction "1_1") (pintype "passive"))
      (node (ref "C5") (pin "1") (pinfunction "1_1") (pintype "passive"))
      (node (ref "C6") (pin "1") (pinfunction "1_1") (pintype "passive"))
      (node (ref "C7") (pin "1") (pinfunction "1_1") (pintype "passive"))
      (node (ref "U2") (pin "2") (pinfunction "VOUT_2") (pintype "passive"))
      (node (ref "U2") (pin "4") (pinfunction "4_4") (pintype "passive"))
      (node (ref "U5") (pin "17") (pinfunction "DVDD_17") (pintype "passive"))
      (node (ref "U5") (pin "23") (pinfunction "DVDD_23") (pintype "passive"))
      (node (ref "U5") (pin "30") (pinfunction "DVDD_30") (pintype "passive"))
      (node (ref "U5") (pin "47") (pinfunction "DVDD_47") (pintype "passive"))
      (node (ref "U5") (pin "57") (pinfunction "DVDD_57") (pintype "passive"))
      (node (ref "U5") (pin "64") (pinfunction "DVDD_64") (pintype "passive"))
    )
    (net (code "79") (name "DVDD-3V3") (class "Default")
      (node (ref "C10") (pin "1") (pinfunction "1_1") (pintype "passive"))
      (node (ref "C11") (pin "1") (pinfunction "1_1") (pintype "passive"))
      (node (ref "C14") (pin "1") (pinfunction "1_1") (pintype "passive"))
      (node (ref "C22") (pin "1") (pinfunction "1_1") (pintype "passive"))
      (node (ref "C23") (pin "1") (pinfunction "1_1") (pintype "passive"))
      (node (ref "C8") (pin "1") (pinfunction "1_1") (pintype "passive"))
      (node (ref "C9") (pin "1") (pinfunction "1_1") (pintype "passive"))
      (node (ref "L4") (pin "2") (pinfunction "2_2") (pintype "passive"))
      (node (ref "U5") (pin "11") (pinfunction "DVDD_IO_11") (pintype "passive"))
      (node (ref "U5") (pin "15") (pinfunction "DVDD_IO_15") (pintype "passive"))
      (node (ref "U5") (pin "21") (pinfunction "DVDD_IO_21") (pintype "passive"))
      (node (ref "U5") (pin "28") (pinfunction "DVDD_IO_28") (pintype "passive"))
      (node (ref "U5") (pin "45") (pinfunction "DVDD_IO_45") (pintype "passive"))
      (node (ref "U5") (pin "56") (pinfunction "DVDD_IO_56") (pintype "passive"))
      (node (ref "U5") (pin "66") (pinfunction "DVDD_IO_66") (pintype "passive"))
    )
    (net (code "80") (name "GND") (class "Default")
      (node (ref "C1") (pin "2") (pinfunction "2_2") (pintype "passive"))
      (node (ref "C10") (pin "2") (pinfunction "2_2") (pintype "passive"))
      (node (ref "C11") (pin "2") (pinfunction "2_2") (pintype "passive"))
      (node (ref "C12") (pin "1") (pinfunction "1_1") (pintype "passive"))
      (node (ref "C13") (pin "2") (pinfunction "2_2") (pintype "passive"))
      (node (ref "C14") (pin "2") (pinfunction "2_2") (pintype "passive"))
      (node (ref "C18") (pin "2") (pinfunction "2_2") (pintype "passive"))
      (node (ref "C2") (pin "2") (pinfunction "2_2") (pintype "passive"))
      (node (ref "C21") (pin "2") (pinfunction "2_2") (pintype "passive"))
      (node (ref "C22") (pin "2") (pinfunction "2_2") (pintype "passive"))
      (node (ref "C23") (pin "2") (pinfunction "2_2") (pintype "passive"))
      (node (ref "C25") (pin "2") (pinfunction "2_2") (pintype "passive"))
      (node (ref "C26") (pin "1") (pinfunction "1_1") (pintype "passive"))
      (node (ref "C27") (pin "2") (pinfunction "2_2") (pintype "passive"))
      (node (ref "C28") (pin "2") (pinfunction "2_2") (pintype "passive"))
      (node (ref "C3") (pin "2") (pinfunction "2_2") (pintype "passive"))
      (node (ref "C31") (pin "1") (pinfunction "1_1") (pintype "passive"))
      (node (ref "C32") (pin "2") (pinfunction "2_2") (pintype "passive"))
      (node (ref "C33") (pin "2") (pinfunction "2_2") (pintype "passive"))
      (node (ref "C35") (pin "2") (pinfunction "2_2") (pintype "passive"))
      (node (ref "C4") (pin "2") (pinfunction "2_2") (pintype "passive"))
      (node (ref "C42") (pin "1") (pinfunction "1_1") (pintype "passive"))
      (node (ref "C43") (pin "1") (pinfunction "1_1") (pintype "passive"))
      (node (ref "C44") (pin "1") (pinfunction "1_1") (pintype "passive"))
      (node (ref "C45") (pin "1") (pinfunction "1_1") (pintype "passive"))
      (node (ref "C46") (pin "1") (pinfunction "1_1") (pintype "passive"))
      (node (ref "C47") (pin "1") (pinfunction "1_1") (pintype "passive"))
      (node (ref "C48") (pin "1") (pinfunction "1_1") (pintype "passive"))
      (node (ref "C49") (pin "1") (pinfunction "1_1") (pintype "passive"))
      (node (ref "C5") (pin "2") (pinfunction "2_2") (pintype "passive"))
      (node (ref "C6") (pin "2") (pinfunction "2_2") (pintype "passive"))
      (node (ref "C7") (pin "2") (pinfunction "2_2") (pintype "passive"))
      (node (ref "C8") (pin "2") (pinfunction "2_2") (pintype "passive"))
      (node (ref "C9") (pin "2") (pinfunction "2_2") (pintype "passive"))
      (node (ref "D1") (pin "2") (pinfunction "2_2") (pintype "passive"))
      (node (ref "J1") (pin "2") (pinfunction "Y_2") (pintype "passive"))
      (node (ref "J2") (pin "2") (pinfunction "Y_2") (pintype "passive"))
      (node (ref "J3") (pin "2") (pinfunction "Y_2") (pintype "passive"))
      (node (ref "L1") (pin "2") (pinfunction "2_2") (pintype "passive"))
      (node (ref "P2") (pin "23") (pinfunction "23_23") (pintype "passive"))
      (node (ref "P2") (pin "24") (pinfunction "24_24") (pintype "passive"))
      (node (ref "P2") (pin "25") (pinfunction "25_25") (pintype "passive"))
      (node (ref "P2") (pin "26") (pinfunction "26_26") (pintype "passive"))
      (node (ref "P3") (pin "18") (pinfunction "18_18") (pintype "passive"))
      (node (ref "P3") (pin "20") (pinfunction "20_20") (pintype "passive"))
      (node (ref "R12") (pin "1") (pinfunction "1_1") (pintype "passive"))
      (node (ref "R2") (pin "2") (pinfunction "2_2") (pintype "passive"))
      (node (ref "R5") (pin "2") (pinfunction "2_2") (pintype "passive"))
      (node (ref "R6") (pin "2") (pinfunction "2_2") (pintype "passive"))
      (node (ref "R9") (pin "2") (pinfunction "2_2") (pintype "passive"))
      (node (ref "U1") (pin "1") (pinfunction "GND_1") (pintype "passive"))
      (node (ref "U2") (pin "1") (pinfunction "GND_1") (pintype "passive"))
      (node (ref "U3") (pin "1") (pinfunction "GND_1") (pintype "passive"))
      (node (ref "U4") (pin "2") (pinfunction "GND_2") (pintype "passive"))
      (node (ref "U5") (pin "13") (pinfunction "DGND_13") (pintype "passive"))
      (node (ref "U5") (pin "16") (pinfunction "DGND_16") (pintype "passive"))
      (node (ref "U5") (pin "22") (pinfunction "DGND_22") (pintype "passive"))
      (node (ref "U5") (pin "29") (pinfunction "DGND_29") (pintype "passive"))
      (node (ref "U5") (pin "46") (pinfunction "DGND_46") (pintype "passive"))
      (node (ref "U5") (pin "51") (pinfunction "DGND_51") (pintype "passive"))
      (node (ref "U5") (pin "58") (pinfunction "DGND_58") (pintype "passive"))
      (node (ref "U5") (pin "65") (pinfunction "DGND_65") (pintype "passive"))
      (node (ref "U5") (pin "95") (pinfunction "XTAL_SEL_95") (pintype "passive"))
      (node (ref "U5") (pin "96") (pinfunction "AGND_96") (pintype "passive"))
      (node (ref "USB1") (pin "A12") (pinfunction "GND_A12") (pintype "passive"))
      (node (ref "USB1") (pin "B12") (pinfunction "GND_B12") (pintype "passive"))
    )
    (net (code "81") (name "Net-(C29-Pad1)") (class "Default")
      (node (ref "C29") (pin "1") (pinfunction "1_1") (pintype "passive"))
      (node (ref "R4") (pin "1") (pinfunction "1_1") (pintype "passive"))
    )
    (net (code "82") (name "Net-(C34-Pad2)") (class "Default")
      (node (ref "C34") (pin "2") (pinfunction "2_2") (pintype "passive"))
      (node (ref "C36") (pin "1") (pinfunction "1_1") (pintype "passive"))
      (node (ref "C43") (pin "2") (pinfunction "2_2") (pintype "passive"))
      (node (ref "L2") (pin "2") (pinfunction "2_2") (pintype "passive"))
      (node (ref "L3") (pin "1") (pinfunction "1_1") (pintype "passive"))
    )
    (net (code "83") (name "Net-(C36-Pad2)") (class "Default")
      (node (ref "C36") (pin "2") (pinfunction "2_2") (pintype "passive"))
      (node (ref "C38") (pin "1") (pinfunction "1_1") (pintype "passive"))
      (node (ref "C48") (pin "2") (pinfunction "2_2") (pintype "passive"))
      (node (ref "L3") (pin "2") (pinfunction "2_2") (pintype "passive"))
      (node (ref "L5") (pin "1") (pinfunction "1_1") (pintype "passive"))
    )
    (net (code "84") (name "Net-(C37-Pad2)") (class "Default")
      (node (ref "C37") (pin "2") (pinfunction "2_2") (pintype "passive"))
      (node (ref "R5") (pin "1") (pinfunction "1_1") (pintype "passive"))
      (node (ref "R7") (pin "2") (pinfunction "2_2") (pintype "passive"))
    )
    (net (code "85") (name "Net-(C39-Pad2)") (class "Default")
      (node (ref "C39") (pin "2") (pinfunction "2_2") (pintype "passive"))
      (node (ref "C40") (pin "1") (pinfunction "1_1") (pintype "passive"))
      (node (ref "C45") (pin "2") (pinfunction "2_2") (pintype "passive"))
      (node (ref "L6") (pin "2") (pinfunction "2_2") (pintype "passive"))
      (node (ref "L7") (pin "1") (pinfunction "1_1") (pintype "passive"))
    )
    (net (code "86") (name "Net-(C40-Pad2)") (class "Default")
      (node (ref "C40") (pin "2") (pinfunction "2_2") (pintype "passive"))
      (node (ref "C41") (pin "1") (pinfunction "1_1") (pintype "passive"))
      (node (ref "C46") (pin "2") (pinfunction "2_2") (pintype "passive"))
      (node (ref "L7") (pin "2") (pinfunction "2_2") (pintype "passive"))
      (node (ref "L8") (pin "1") (pinfunction "1_1") (pintype "passive"))
    )
    (net (code "87") (name "Net-(D1-Pad1)") (class "Default")
      (node (ref "D1") (pin "1") (pinfunction "1_1") (pintype "passive"))
      (node (ref "R1") (pin "1") (pinfunction "1_1") (pintype "passive"))
    )
    (net (code "88") (name "Net-(D2-Pad1)") (class "Default")
      (node (ref "D2") (pin "1") (pintype "passive"))
      (node (ref "USB1") (pin "A9") (pinfunction "VBUS_A9") (pintype "passive"))
      (node (ref "USB1") (pin "B9") (pinfunction "VBUS_B9") (pintype "passive"))
    )
    (net (code "89") (name "Net-(D2-Pad2)") (class "Default")
      (node (ref "D2") (pin "2") (pintype "passive"))
      (node (ref "SW1") (pin "2") (pinfunction "2_2") (pintype "passive"))
    )
    (net (code "90") (name "Net-(F1-Pad1)") (class "Default")
      (node (ref "F1") (pin "1") (pinfunction "1_1") (pintype "passive"))
      (node (ref "R1") (pin "2") (pinfunction "2_2") (pintype "passive"))
      (node (ref "SW1") (pin "1") (pinfunction "1_1") (pintype "passive"))
    )
    (net (code "91") (name "Net-(J1-X)") (class "Default")
      (node (ref "J1") (pin "1") (pinfunction "X_1") (pintype "passive"))
      (node (ref "R2") (pin "1") (pinfunction "1_1") (pintype "passive"))
      (node (ref "W9") (pin "1") (pinfunction "1_1") (pintype "power_in"))
    )
    (net (code "92") (name "Net-(J2-X)") (class "Default")
      (node (ref "C41") (pin "2") (pinfunction "2_2") (pintype "passive"))
      (node (ref "C47") (pin "2") (pinfunction "2_2") (pintype "passive"))
      (node (ref "J2") (pin "1") (pinfunction "X_1") (pintype "passive"))
      (node (ref "L8") (pin "2") (pinfunction "2_2") (pintype "passive"))
    )
    (net (code "93") (name "Net-(J3-X)") (class "Default")
      (node (ref "C38") (pin "2") (pinfunction "2_2") (pintype "passive"))
      (node (ref "C49") (pin "2") (pinfunction "2_2") (pintype "passive"))
      (node (ref "J3") (pin "1") (pinfunction "X_1") (pintype "passive"))
      (node (ref "L5") (pin "2") (pinfunction "2_2") (pintype "passive"))
    )
    (net (code "94") (name "Net-(R6-Pad1)") (class "Default")
      (node (ref "R6") (pin "1") (pinfunction "1_1") (pintype "passive"))
      (node (ref "R7") (pin "1") (pinfunction "1_1") (pintype "passive"))
      (node (ref "W9") (pin "2") (pinfunction "2_2") (pintype "power_in"))
    )
    (net (code "95") (name "Net-(U1-VIN)") (class "Default")
      (node (ref "C13") (pin "1") (pinfunction "1_1") (pintype "passive"))
      (node (ref "C18") (pin "1") (pinfunction "1_1") (pintype "passive"))
      (node (ref "C25") (pin "1") (pinfunction "1_1") (pintype "passive"))
      (node (ref "C28") (pin "1") (pinfunction "1_1") (pintype "passive"))
      (node (ref "F1") (pin "2") (pinfunction "2_2") (pintype "passive"))
      (node (ref "U1") (pin "3") (pinfunction "VIN_3") (pintype "passive"))
      (node (ref "U2") (pin "3") (pinfunction "VIN_3") (pintype "passive"))
      (node (ref "U3") (pin "3") (pinfunction "VIN_3") (pintype "passive"))
    )
    (net (code "96") (name "Net-(U4-OUT)") (class "Default")
      (node (ref "U4") (pin "3") (pinfunction "OUT_3") (pintype "passive"))
      (node (ref "W9") (pin "3") (pinfunction "3_3") (pintype "power_in"))
    )
    (net (code "97") (name "Net-(U4-VCC)") (class "Default")
      (node (ref "C35") (pin "1") (pinfunction "1_1") (pintype "passive"))
      (node (ref "L9") (pin "1") (pinfunction "1_1") (pintype "passive"))
      (node (ref "U4") (pin "4") (pinfunction "VCC_4") (pintype "passive"))
    )
    (net (code "98") (name "Net-(U5-DAC_RSET)") (class "Default")
      (node (ref "R8") (pin "2") (pinfunction "2_2") (pintype "passive"))
      (node (ref "U5") (pin "84") (pinfunction "DAC_RSET_84") (pintype "passive"))
    )
    (net (code "99") (name "Net-(U5-IOUT)") (class "Default")
      (node (ref "C39") (pin "1") (pinfunction "1_1") (pintype "passive"))
      (node (ref "C44") (pin "2") (pinfunction "2_2") (pintype "passive"))
      (node (ref "L6") (pin "1") (pinfunction "1_1") (pintype "passive"))
      (node (ref "R9") (pin "1") (pinfunction "1_1") (pintype "passive"))
      (node (ref "U5") (pin "81") (pinfunction "IOUT_81") (pintype "passive"))
    )
    (net (code "100") (name "Net-(U5-PLL_LOOP_FILTER)") (class "Default")
      (node (ref "C30") (pin "1") (pinfunction "1_1") (pintype "passive"))
      (node (ref "R4") (pin "2") (pinfunction "2_2") (pintype "passive"))
      (node (ref "U5") (pin "2") (pinfunction "PLL_LOOP_FILTER_2") (pintype "passive"))
    )
    (net (code "101") (name "Net-(U5-REF_CLK)") (class "Default")
      (node (ref "C37") (pin "1") (pinfunction "1_1") (pintype "passive"))
      (node (ref "U5") (pin "90") (pinfunction "REF_CLK_90") (pintype "passive"))
    )
    (net (code "102") (name "Net-(U5-SYNC_IN+)") (class "Default")
      (node (ref "P1") (pin "5") (pinfunction "5_5") (pintype "passive"))
      (node (ref "U5") (pin "7") (pinfunction "SYNC_IN+_7") (pintype "passive"))
    )
    (net (code "103") (name "Net-(U5-SYNC_IN-)") (class "Default")
      (node (ref "P1") (pin "4") (pinfunction "4_4") (pintype "passive"))
      (node (ref "U5") (pin "8") (pinfunction "SYNC_IN-_8") (pintype "passive"))
    )
    (net (code "104") (name "Net-(U5-SYNC_OUT+)") (class "Default")
      (node (ref "P1") (pin "3") (pinfunction "3_3") (pintype "passive"))
      (node (ref "U5") (pin "9") (pinfunction "SYNC_OUT+_9") (pintype "passive"))
    )
    (net (code "105") (name "Net-(U5-SYNC_OUT-)") (class "Default")
      (node (ref "P1") (pin "2") (pinfunction "2_2") (pintype "passive"))
      (node (ref "U5") (pin "10") (pinfunction "SYNC_OUT-_10") (pintype "passive"))
    )
    (net (code "106") (name "Net-(U5-SYNC_SMP_RESET)") (class "Default")
      (node (ref "P1") (pin "1") (pinfunction "1_1") (pintype "passive"))
      (node (ref "U5") (pin "12") (pinfunction "SYNC_SMP_RESET_12") (pintype "passive"))
    )
    (net (code "107") (name "Net-(U5-{slash}IOUT)") (class "Default")
      (node (ref "C34") (pin "1") (pinfunction "1_1") (pintype "passive"))
      (node (ref "C42") (pin "2") (pinfunction "2_2") (pintype "passive"))
      (node (ref "L2") (pin "1") (pinfunction "1_1") (pintype "passive"))
      (node (ref "R12") (pin "2") (pinfunction "2_2") (pintype "passive"))
      (node (ref "U5") (pin "80") (pinfunction "/IOUT_80") (pintype "passive"))
    )
    (net (code "108") (name "Net-(U5-{slash}REF_CLK)") (class "Default")
      (node (ref "C33") (pin "1") (pinfunction "1_1") (pintype "passive"))
      (node (ref "U5") (pin "91") (pinfunction "/REF_CLK_91") (pintype "passive"))
    )
    (net (code "109") (name "unconnected-(P2-Pad17)") (class "Default")
      (node (ref "P2") (pin "17") (pinfunction "17_17") (pintype "passive"))
    )
    (net (code "110") (name "unconnected-(P2-Pad19)") (class "Default")
      (node (ref "P2") (pin "19") (pinfunction "19_19") (pintype "passive"))
    )
    (net (code "111") (name "unconnected-(P2-Pad21)") (class "Default")
      (node (ref "P2") (pin "21") (pinfunction "21_21") (pintype "passive"))
    )
    (net (code "112") (name "unconnected-(R14-Pad7)") (class "Default")
      (node (ref "R14") (pin "7") (pinfunction "7_7") (pintype "passive"))
    )
    (net (code "113") (name "unconnected-(R14-Pad8)") (class "Default")
      (node (ref "R14") (pin "8") (pinfunction "8_8") (pintype "passive"))
    )
    (net (code "114") (name "unconnected-(R19-Pad5)") (class "Default")
      (node (ref "R19") (pin "5") (pinfunction "5_5") (pintype "passive"))
    )
    (net (code "115") (name "unconnected-(R19-Pad6)") (class "Default")
      (node (ref "R19") (pin "6") (pinfunction "6_6") (pintype "passive"))
    )
    (net (code "116") (name "unconnected-(R19-Pad7)") (class "Default")
      (node (ref "R19") (pin "7") (pinfunction "7_7") (pintype "passive"))
    )
    (net (code "117") (name "unconnected-(R19-Pad8)") (class "Default")
      (node (ref "R19") (pin "8") (pinfunction "8_8") (pintype "passive"))
    )
    (net (code "118") (name "unconnected-(SW1-Pad3)") (class "Default")
      (node (ref "SW1") (pin "3") (pinfunction "3_3") (pintype "passive"))
    )
    (net (code "119") (name "unconnected-(SW1-Pad4)") (class "Default")
      (node (ref "SW1") (pin "4") (pinfunction "4_4") (pintype "passive"))
    )
    (net (code "120") (name "unconnected-(SW1-Pad5)") (class "Default")
      (node (ref "SW1") (pin "5") (pinfunction "5_5") (pintype "passive"))
    )
    (net (code "121") (name "unconnected-(SW1-Pad6)") (class "Default")
      (node (ref "SW1") (pin "6") (pinfunction "6_6") (pintype "passive"))
    )
    (net (code "122") (name "unconnected-(U4-NC-Pad1)") (class "Default")
      (node (ref "U4") (pin "1") (pinfunction "NC_1") (pintype "passive"))
    )
    (net (code "123") (name "unconnected-(U5-NC-Pad1)") (class "Default")
      (node (ref "U5") (pin "1") (pinfunction "NC_1") (pintype "passive"))
    )
    (net (code "124") (name "unconnected-(U5-NC-Pad20)") (class "Default")
      (node (ref "U5") (pin "20") (pinfunction "NC_20") (pintype "passive"))
    )
    (net (code "125") (name "unconnected-(U5-NC-Pad72)") (class "Default")
      (node (ref "U5") (pin "72") (pinfunction "NC_72") (pintype "passive"))
    )
    (net (code "126") (name "unconnected-(U5-NC-Pad86)") (class "Default")
      (node (ref "U5") (pin "86") (pinfunction "NC_86") (pintype "passive"))
    )
    (net (code "127") (name "unconnected-(U5-NC-Pad87)") (class "Default")
      (node (ref "U5") (pin "87") (pinfunction "NC_87") (pintype "passive"))
    )
    (net (code "128") (name "unconnected-(U5-NC-Pad93)") (class "Default")
      (node (ref "U5") (pin "93") (pinfunction "NC_93") (pintype "passive"))
    )
    (net (code "129") (name "unconnected-(U5-NC-Pad97)") (class "Default")
      (node (ref "U5") (pin "97") (pinfunction "NC_97") (pintype "passive"))
    )
    (net (code "130") (name "unconnected-(U5-NC-Pad98)") (class "Default")
      (node (ref "U5") (pin "98") (pinfunction "NC_98") (pintype "passive"))
    )
    (net (code "131") (name "unconnected-(U5-NC-Pad99)") (class "Default")
      (node (ref "U5") (pin "99") (pinfunction "NC_99") (pintype "passive"))
    )
    (net (code "132") (name "unconnected-(U5-NC-Pad100)") (class "Default")
      (node (ref "U5") (pin "100") (pinfunction "NC_100") (pintype "passive"))
    )
    (net (code "133") (name "unconnected-(U5-XTAL_OUT-Pad94)") (class "Default")
      (node (ref "U5") (pin "94") (pinfunction "XTAL_OUT_94") (pintype "passive"))
    )
    (net (code "134") (name "unconnected-(USB1-CC1-PadA5)") (class "Default")
      (node (ref "USB1") (pin "A5") (pinfunction "CC1_A5") (pintype "passive"))
    )
    (net (code "135") (name "unconnected-(USB1-CC2-PadB5)") (class "Default")
      (node (ref "USB1") (pin "B5") (pinfunction "CC2_B5") (pintype "passive"))
    )
  )
)
